# PT100_Module.net
KiCad netlist of a schematic drawn in EAGLE
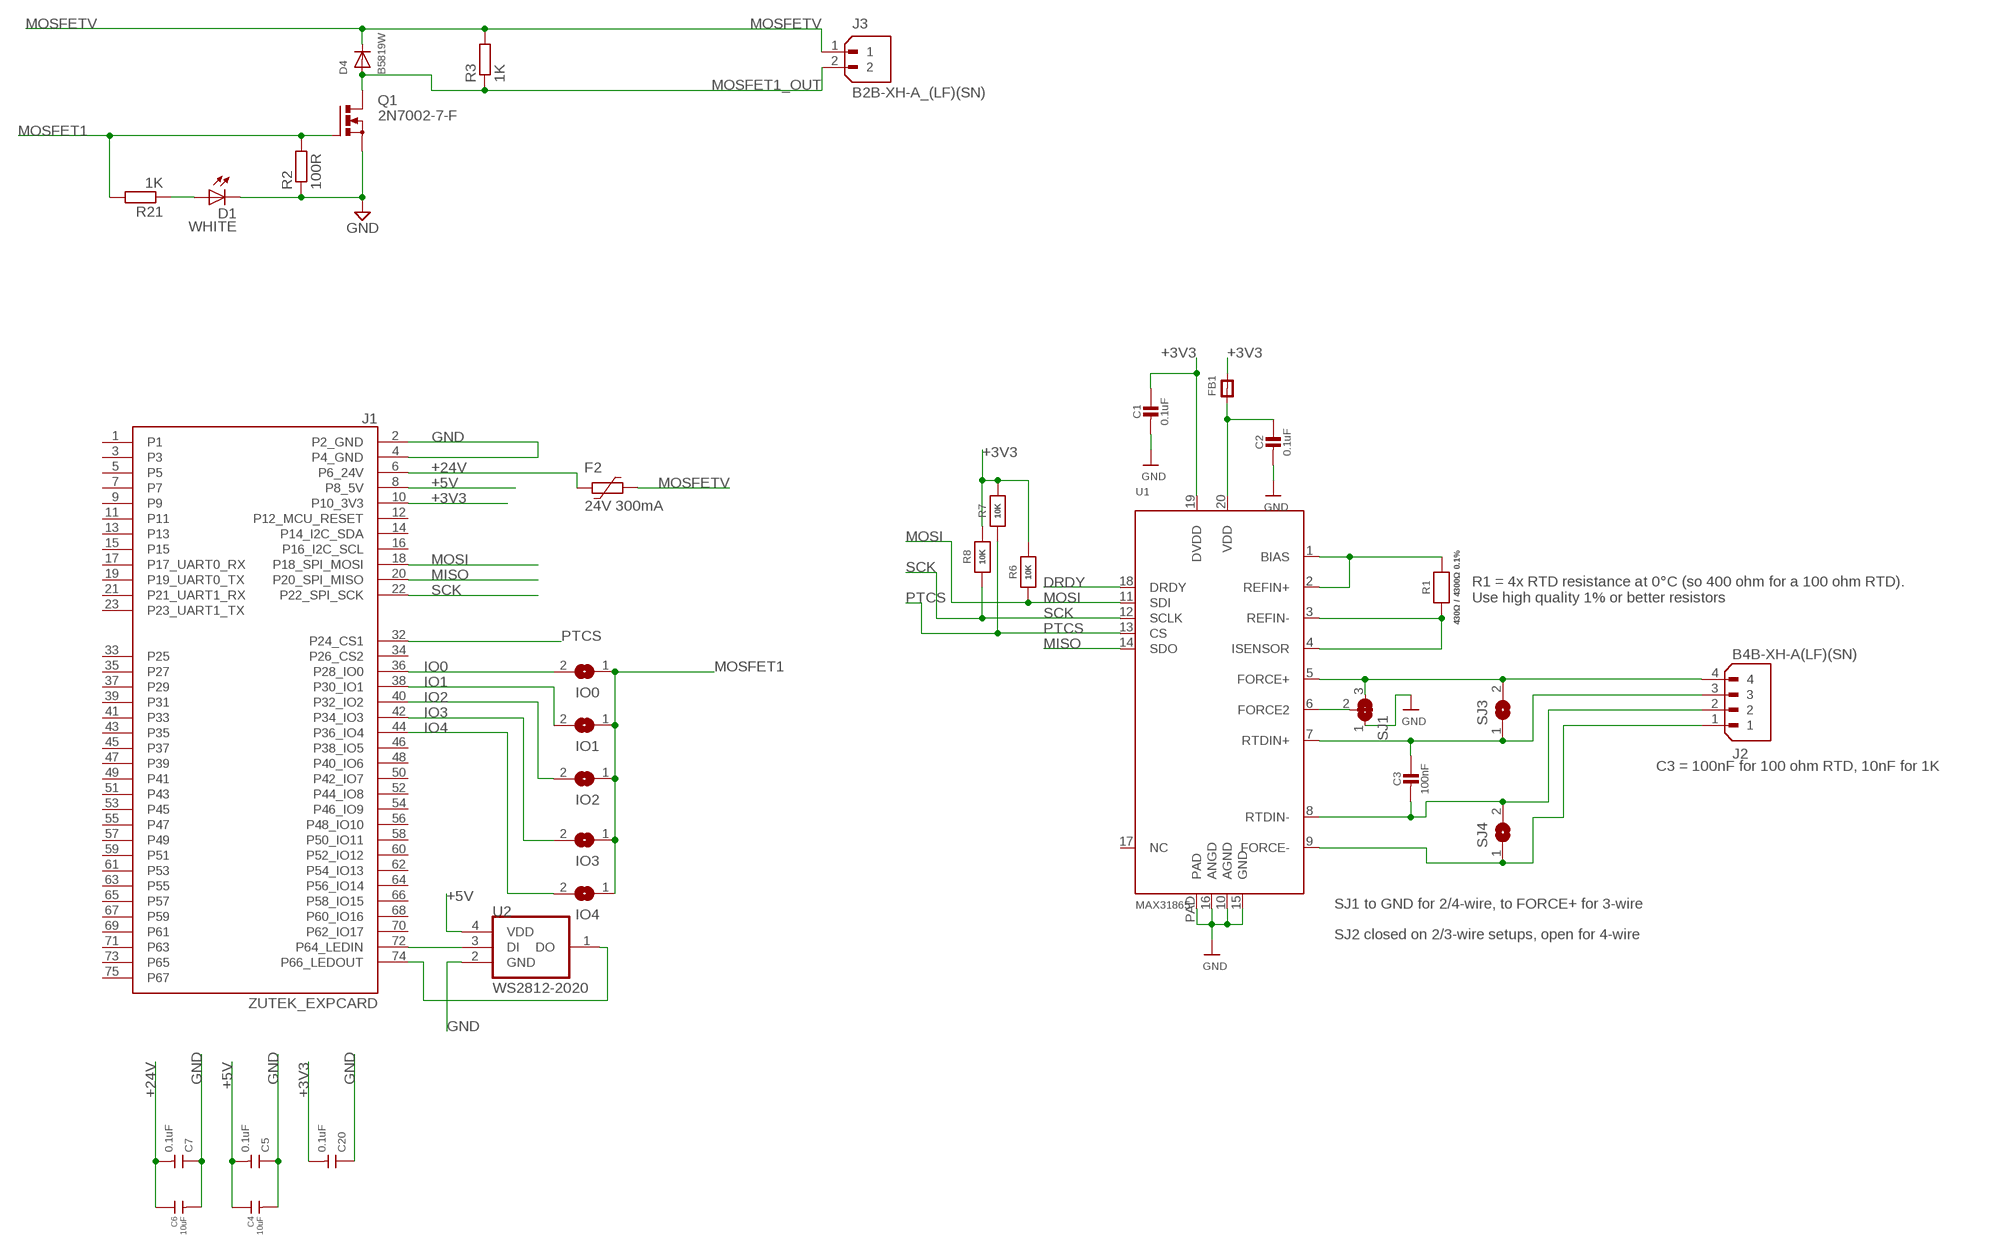
[diagram p0: schematic, sheet 1]

(export (version "E")
  (design (tool "Eeschema 10.0.6"))
  (components
    (comp (ref "C1")
      (value "0.1uF")
      (footprint "eagle-import:0805-NO")
      (libsource (lib "eagle-import") (part "CAP_CERAMIC0805-NOOUTLINE"))
    )
    (comp (ref "C2")
      (value "0.1uF")
      (footprint "eagle-import:0805-NO")
      (libsource (lib "eagle-import") (part "CAP_CERAMIC0805-NOOUTLINE"))
    )
    (comp (ref "C3")
      (value "100nF")
      (footprint "eagle-import:0805-NO")
      (libsource (lib "eagle-import") (part "CAP_CERAMIC0805-NOOUTLINE"))
    )
    (comp (ref "C4")
      (value "10uF")
      (footprint "eagle-import:C1206")
      (libsource (lib "eagle-import") (part "C-1206"))
    )
    (comp (ref "C5")
      (value "0.1uF")
      (footprint "eagle-import:DISCRETE_C0603")
      (libsource (lib "eagle-import") (part "DISCRETE_C-0603"))
    )
    (comp (ref "C6")
      (value "10uF")
      (footprint "eagle-import:C1206")
      (libsource (lib "eagle-import") (part "C-1206"))
    )
    (comp (ref "C7")
      (value "0.1uF")
      (footprint "eagle-import:DISCRETE_C0603")
      (libsource (lib "eagle-import") (part "DISCRETE_C-0603"))
    )
    (comp (ref "C20")
      (value "0.1uF")
      (footprint "eagle-import:DISCRETE_C0603")
      (libsource (lib "eagle-import") (part "DISCRETE_C-0603"))
    )
    (comp (ref "D1")
      (value "WHITE")
      (footprint "eagle-import:CHIP-LED0603")
      (libsource (lib "eagle-import") (part "LEDCHIP-LED0603"))
    )
    (comp (ref "D4")
      (value "B5819W")
      (footprint "eagle-import:SOD123FL")
      (fields (field (name "MF") "Microdiode Electronics"))
      (libsource (lib "eagle-import") (part "B5819W"))
    )
    (comp (ref "F2")
      (value "24V 300mA")
      (footprint "eagle-import:1206L")
      (fields (field (name "MF") "Littelfuse") (field (name "MPN") "1206L050"))
      (libsource (lib "eagle-import") (part "?1206L050"))
    )
    (comp (ref "FB1")
      (value "FERRITE-0805NO")
      (footprint "eagle-import:0805-NO")
      (libsource (lib "eagle-import") (part "FERRITE-0805NO"))
    )
    (comp (ref "IO0")
      (value "SOLDERJUMPERCLOSED")
      (footprint "eagle-import:SOLDERJUMPER_CLOSEDWIRE")
      (libsource (lib "eagle-import") (part "SOLDERJUMPERCLOSED"))
    )
    (comp (ref "IO1")
      (value "SOLDERJUMPER")
      (footprint "eagle-import:SOLDERJUMPER_ARROW_NOPASTE")
      (libsource (lib "eagle-import") (part "SOLDERJUMPER"))
    )
    (comp (ref "IO2")
      (value "SOLDERJUMPER")
      (footprint "eagle-import:SOLDERJUMPER_ARROW_NOPASTE")
      (libsource (lib "eagle-import") (part "SOLDERJUMPER"))
    )
    (comp (ref "IO3")
      (value "SOLDERJUMPER")
      (footprint "eagle-import:SOLDERJUMPER_ARROW_NOPASTE")
      (libsource (lib "eagle-import") (part "SOLDERJUMPER"))
    )
    (comp (ref "IO4")
      (value "SOLDERJUMPER")
      (footprint "eagle-import:SOLDERJUMPER_ARROW_NOPASTE")
      (libsource (lib "eagle-import") (part "SOLDERJUMPER"))
    )
    (comp (ref "J1")
      (value "ZUTEK_EXPCARD")
      (footprint "eagle-import:M.2-CARD-E-22-ZUTEK")
      (libsource (lib "eagle-import") (part "ZUTEK_EXPCARD"))
    )
    (comp (ref "J2")
      (value "B4B-XH-A(LF)(SN)")
      (footprint "eagle-import:JST_B4B-XH-A(LF)(SN)")
      (fields (field (name "MF") "JST Sales") (field (name "MP") "B4B-XH-A (LF)(SN)"))
      (libsource (lib "eagle-import") (part "B4B-XH-A(LF)(SN)"))
    )
    (comp (ref "J3")
      (value "B2B-XH-A_(LF)(SN)")
      (footprint "eagle-import:JST_B2B-XH-A_(LF)(SN)")
      (fields (field (name "MF") "JST Sales") (field (name "MP") "B2B-XH-A (LF)(SN)"))
      (libsource (lib "eagle-import") (part "B2B-XH-A_(LF)(SN)"))
    )
    (comp (ref "Q1")
      (value "2N7002-7-F")
      (footprint "eagle-import:SOT-23")
      (libsource (lib "eagle-import") (part "2N7002-7-F"))
    )
    (comp (ref "R1")
      (value "430Ω / 4300Ω 0.1%")
      (footprint "eagle-import:0805-NO")
      (libsource (lib "eagle-import") (part "RESISTOR0805_NOOUTLINE"))
    )
    (comp (ref "R2")
      (value "100R")
      (footprint "eagle-import:R0402")
      (libsource (lib "eagle-import") (part "R-EU_R0402"))
    )
    (comp (ref "R3")
      (value "1K")
      (footprint "eagle-import:R0402")
      (fields (field (name "LCSC_PART") "C11702 "))
      (libsource (lib "eagle-import") (part "R-EU_R0402"))
    )
    (comp (ref "R6")
      (value "10K")
      (footprint "eagle-import:_0402")
      (libsource (lib "eagle-import") (part "RESISTOR_0402"))
    )
    (comp (ref "R7")
      (value "10K")
      (footprint "eagle-import:_0402")
      (libsource (lib "eagle-import") (part "RESISTOR_0402"))
    )
    (comp (ref "R8")
      (value "10K")
      (footprint "eagle-import:_0402")
      (libsource (lib "eagle-import") (part "RESISTOR_0402"))
    )
    (comp (ref "R21")
      (value "1K")
      (footprint "eagle-import:R0402")
      (libsource (lib "eagle-import") (part "R-EU_R0402"))
    )
    (comp (ref "SJ1")
      (value "SOLDERJUMPER_2WAY")
      (footprint "eagle-import:SOLDERJUMPER_2WAY_OPEN_NOPASTE")
      (libsource (lib "eagle-import") (part "SOLDERJUMPER_2WAY"))
    )
    (comp (ref "SJ3")
      (value "SOLDERJUMPER")
      (footprint "eagle-import:SOLDERJUMPER_ARROW_NOPASTE")
      (libsource (lib "eagle-import") (part "SOLDERJUMPER"))
    )
    (comp (ref "SJ4")
      (value "SOLDERJUMPER")
      (footprint "eagle-import:SOLDERJUMPER_ARROW_NOPASTE")
      (libsource (lib "eagle-import") (part "SOLDERJUMPER"))
    )
    (comp (ref "U1")
      (value "MAX31865")
      (footprint "eagle-import:QFN20_4MM_0.65MM")
      (libsource (lib "eagle-import") (part "TEMP_MAX31865"))
    )
    (comp (ref "U2")
      (value "WS2812-2020")
      (footprint "eagle-import:LED_WS2812-2020")
      (fields (field (name "MF") "Worldsemi"))
      (libsource (lib "eagle-import") (part "WS2812-2020"))
    )
  )
  (nets
    (net (code "1") (name "/+3V3") (class "Default")
      (node (ref "C1") (pin "1") (pinfunction "1_1") (pintype "passive"))
      (node (ref "C20") (pin "2") (pinfunction "2_2") (pintype "passive"))
      (node (ref "FB1") (pin "2") (pinfunction "P$2_2") (pintype "passive"))
      (node (ref "J1") (pin "10") (pinfunction "P10_3V3_10") (pintype "bidirectional"))
      (node (ref "R6") (pin "2") (pinfunction "2_2") (pintype "passive"))
      (node (ref "R7") (pin "2") (pinfunction "2_2") (pintype "passive"))
      (node (ref "R8") (pin "2") (pinfunction "2_2") (pintype "passive"))
      (node (ref "U1") (pin "19") (pinfunction "DVDD_19") (pintype "power_in"))
    )
    (net (code "2") (name "/+5V") (class "Default")
      (node (ref "C4") (pin "1") (pinfunction "1_1") (pintype "passive"))
      (node (ref "C5") (pin "2") (pinfunction "2_2") (pintype "passive"))
      (node (ref "J1") (pin "8") (pinfunction "P8_5V_8") (pintype "bidirectional"))
      (node (ref "U2") (pin "4") (pinfunction "VDD_4") (pintype "power_in"))
    )
    (net (code "3") (name "/+24V") (class "Default")
      (node (ref "C6") (pin "1") (pinfunction "1_1") (pintype "passive"))
      (node (ref "C7") (pin "2") (pinfunction "2_2") (pintype "passive"))
      (node (ref "F2") (pin "2") (pinfunction "2_2") (pintype "passive"))
      (node (ref "J1") (pin "6") (pinfunction "P6_24V_6") (pintype "bidirectional"))
    )
    (net (code "4") (name "/DRDY") (class "Default")
      (node (ref "U1") (pin "18") (pinfunction "DRDY_18") (pintype "output"))
    )
    (net (code "5") (name "/IO0") (class "Default")
      (node (ref "IO0") (pin "2") (pinfunction "2_2") (pintype "passive"))
      (node (ref "J1") (pin "36") (pinfunction "P28_IO0_36") (pintype "bidirectional"))
    )
    (net (code "6") (name "/IO1") (class "Default")
      (node (ref "IO1") (pin "2") (pinfunction "2_2") (pintype "passive"))
      (node (ref "J1") (pin "38") (pinfunction "P30_IO1_38") (pintype "bidirectional"))
    )
    (net (code "7") (name "/IO2") (class "Default")
      (node (ref "IO2") (pin "2") (pinfunction "2_2") (pintype "passive"))
      (node (ref "J1") (pin "40") (pinfunction "P32_IO2_40") (pintype "bidirectional"))
    )
    (net (code "8") (name "/IO3") (class "Default")
      (node (ref "IO3") (pin "2") (pinfunction "2_2") (pintype "passive"))
      (node (ref "J1") (pin "42") (pinfunction "P34_IO3_42") (pintype "bidirectional"))
    )
    (net (code "9") (name "/IO4") (class "Default")
      (node (ref "IO4") (pin "2") (pinfunction "2_2") (pintype "passive"))
      (node (ref "J1") (pin "44") (pinfunction "P36_IO4_44") (pintype "bidirectional"))
    )
    (net (code "10") (name "/MISO") (class "Default")
      (node (ref "J1") (pin "20") (pinfunction "P20_SPI_MISO_20") (pintype "bidirectional"))
      (node (ref "U1") (pin "14") (pinfunction "SDO_14") (pintype "output"))
    )
    (net (code "11") (name "/MOSFET1") (class "Default")
      (node (ref "IO0") (pin "1") (pinfunction "1_1") (pintype "passive"))
      (node (ref "IO1") (pin "1") (pinfunction "1_1") (pintype "passive"))
      (node (ref "IO2") (pin "1") (pinfunction "1_1") (pintype "passive"))
      (node (ref "IO3") (pin "1") (pinfunction "1_1") (pintype "passive"))
      (node (ref "IO4") (pin "1") (pinfunction "1_1") (pintype "passive"))
      (node (ref "Q1") (pin "P1") (pinfunction "G_P1") (pintype "passive"))
      (node (ref "R2") (pin "2") (pinfunction "2_2") (pintype "passive"))
      (node (ref "R21") (pin "2") (pinfunction "2_2") (pintype "passive"))
    )
    (net (code "12") (name "/MOSFET1_OUT") (class "Default")
      (node (ref "D4") (pin "A") (pinfunction "A_A") (pintype "passive"))
      (node (ref "J3") (pin "2") (pinfunction "2_2") (pintype "passive"))
      (node (ref "Q1") (pin "P3") (pinfunction "D_P3") (pintype "passive"))
      (node (ref "R3") (pin "1") (pinfunction "1_1") (pintype "passive"))
    )
    (net (code "13") (name "/MOSFETV") (class "Default")
      (node (ref "D4") (pin "C") (pinfunction "C_C") (pintype "passive"))
      (node (ref "F2") (pin "1") (pinfunction "1_1") (pintype "passive"))
      (node (ref "J3") (pin "1") (pinfunction "1_1") (pintype "passive"))
      (node (ref "R3") (pin "2") (pinfunction "2_2") (pintype "passive"))
    )
    (net (code "14") (name "/MOSI") (class "Default")
      (node (ref "J1") (pin "18") (pinfunction "P18_SPI_MOSI_18") (pintype "bidirectional"))
      (node (ref "R6") (pin "1") (pinfunction "1_1") (pintype "passive"))
      (node (ref "U1") (pin "11") (pinfunction "SDI_11") (pintype "input"))
    )
    (net (code "15") (name "/PTCS") (class "Default")
      (node (ref "J1") (pin "32") (pinfunction "P24_CS1_32") (pintype "bidirectional"))
      (node (ref "R7") (pin "1") (pinfunction "1_1") (pintype "passive"))
      (node (ref "U1") (pin "13") (pinfunction "CS_13") (pintype "input"))
    )
    (net (code "16") (name "/SCK") (class "Default")
      (node (ref "J1") (pin "22") (pinfunction "P22_SPI_SCK_22") (pintype "bidirectional"))
      (node (ref "R8") (pin "1") (pinfunction "1_1") (pintype "passive"))
      (node (ref "U1") (pin "12") (pinfunction "SCLK_12") (pintype "input"))
    )
    (net (code "17") (name "GND") (class "Default")
      (node (ref "C1") (pin "2") (pinfunction "2_2") (pintype "passive"))
      (node (ref "C2") (pin "2") (pinfunction "2_2") (pintype "passive"))
      (node (ref "C20") (pin "1") (pinfunction "1_1") (pintype "passive"))
      (node (ref "C4") (pin "2") (pinfunction "2_2") (pintype "passive"))
      (node (ref "C5") (pin "1") (pinfunction "1_1") (pintype "passive"))
      (node (ref "C6") (pin "2") (pinfunction "2_2") (pintype "passive"))
      (node (ref "C7") (pin "1") (pinfunction "1_1") (pintype "passive"))
      (node (ref "D1") (pin "C") (pinfunction "C_C") (pintype "passive"))
      (node (ref "J1") (pin "2") (pinfunction "P2_GND_2") (pintype "bidirectional"))
      (node (ref "J1") (pin "4") (pinfunction "P4_GND_4") (pintype "bidirectional"))
      (node (ref "Q1") (pin "P2") (pinfunction "S_P2") (pintype "passive"))
      (node (ref "R2") (pin "1") (pinfunction "1_1") (pintype "passive"))
      (node (ref "SJ1") (pin "1") (pinfunction "1_1") (pintype "passive"))
      (node (ref "U1") (pin "10") (pinfunction "AGND_10") (pintype "power_in"))
      (node (ref "U1") (pin "15") (pinfunction "GND_15") (pintype "power_in"))
      (node (ref "U1") (pin "16") (pinfunction "ANGD_16") (pintype "power_in"))
      (node (ref "U1") (pin "PAD") (pinfunction "PAD_PAD") (pintype "power_in"))
      (node (ref "U2") (pin "2") (pinfunction "GND_2") (pintype "power_in"))
    )
    (net (code "18") (name "Net-(D1-PadA)") (class "Default")
      (node (ref "D1") (pin "A") (pinfunction "A_A") (pintype "passive"))
      (node (ref "R21") (pin "1") (pinfunction "1_1") (pintype "passive"))
    )
    (net (code "19") (name "Net-(FB1-P$1)") (class "Default")
      (node (ref "C2") (pin "1") (pinfunction "1_1") (pintype "passive"))
      (node (ref "FB1") (pin "1") (pinfunction "P$1_1") (pintype "passive"))
      (node (ref "U1") (pin "20") (pinfunction "VDD_20") (pintype "power_in"))
    )
    (net (code "20") (name "Net-(J1-P64_LEDIN)") (class "Default")
      (node (ref "J1") (pin "72") (pinfunction "P64_LEDIN_72") (pintype "bidirectional"))
      (node (ref "U2") (pin "3") (pinfunction "DI_3") (pintype "input"))
    )
    (net (code "21") (name "Net-(J1-P66_LEDOUT)") (class "Default")
      (node (ref "J1") (pin "74") (pinfunction "P66_LEDOUT_74") (pintype "bidirectional"))
      (node (ref "U2") (pin "1") (pinfunction "DO_1") (pintype "output"))
    )
    (net (code "22") (name "Net-(U1-BIAS)") (class "Default")
      (node (ref "R1") (pin "2") (pinfunction "2_2") (pintype "passive"))
      (node (ref "U1") (pin "1") (pinfunction "BIAS_1") (pintype "output"))
      (node (ref "U1") (pin "2") (pinfunction "REFIN+_2") (pintype "bidirectional"))
    )
    (net (code "23") (name "Net-(U1-FORCE+)") (class "Default")
      (node (ref "J2") (pin "4") (pinfunction "4_4") (pintype "passive"))
      (node (ref "SJ1") (pin "3") (pinfunction "3_3") (pintype "passive"))
      (node (ref "SJ3") (pin "2") (pinfunction "2_2") (pintype "passive"))
      (node (ref "U1") (pin "5") (pinfunction "FORCE+_5") (pintype "output"))
    )
    (net (code "24") (name "Net-(U1-FORCE-)") (class "Default")
      (node (ref "J2") (pin "1") (pinfunction "1_1") (pintype "passive"))
      (node (ref "SJ4") (pin "1") (pinfunction "1_1") (pintype "passive"))
      (node (ref "U1") (pin "9") (pinfunction "FORCE-_9") (pintype "input"))
    )
    (net (code "25") (name "Net-(U1-FORCE2)") (class "Default")
      (node (ref "SJ1") (pin "2") (pinfunction "2_2") (pintype "passive"))
      (node (ref "U1") (pin "6") (pinfunction "FORCE2_6") (pintype "bidirectional"))
    )
    (net (code "26") (name "Net-(U1-ISENSOR)") (class "Default")
      (node (ref "R1") (pin "1") (pinfunction "1_1") (pintype "passive"))
      (node (ref "U1") (pin "3") (pinfunction "REFIN-_3") (pintype "bidirectional"))
      (node (ref "U1") (pin "4") (pinfunction "ISENSOR_4") (pintype "input"))
    )
    (net (code "27") (name "Net-(U1-RTDIN+)") (class "Default")
      (node (ref "C3") (pin "1") (pinfunction "1_1") (pintype "passive"))
      (node (ref "J2") (pin "3") (pinfunction "3_3") (pintype "passive"))
      (node (ref "SJ3") (pin "1") (pinfunction "1_1") (pintype "passive"))
      (node (ref "U1") (pin "7") (pinfunction "RTDIN+_7") (pintype "bidirectional"))
    )
    (net (code "28") (name "Net-(U1-RTDIN-)") (class "Default")
      (node (ref "C3") (pin "2") (pinfunction "2_2") (pintype "passive"))
      (node (ref "J2") (pin "2") (pinfunction "2_2") (pintype "passive"))
      (node (ref "SJ4") (pin "2") (pinfunction "2_2") (pintype "passive"))
      (node (ref "U1") (pin "8") (pinfunction "RTDIN-_8") (pintype "bidirectional"))
    )
    (net (code "29") (name "unconnected-(J1-P1-Pad1)") (class "Default")
      (node (ref "J1") (pin "1") (pinfunction "P1_1") (pintype "bidirectional"))
    )
    (net (code "30") (name "unconnected-(J1-P3-Pad3)") (class "Default")
      (node (ref "J1") (pin "3") (pinfunction "P3_3") (pintype "bidirectional"))
    )
    (net (code "31") (name "unconnected-(J1-P5-Pad5)") (class "Default")
      (node (ref "J1") (pin "5") (pinfunction "P5_5") (pintype "bidirectional"))
    )
    (net (code "32") (name "unconnected-(J1-P7-Pad7)") (class "Default")
      (node (ref "J1") (pin "7") (pinfunction "P7_7") (pintype "bidirectional"))
    )
    (net (code "33") (name "unconnected-(J1-P9-Pad9)") (class "Default")
      (node (ref "J1") (pin "9") (pinfunction "P9_9") (pintype "bidirectional"))
    )
    (net (code "34") (name "unconnected-(J1-P11-Pad11)") (class "Default")
      (node (ref "J1") (pin "11") (pinfunction "P11_11") (pintype "bidirectional"))
    )
    (net (code "35") (name "unconnected-(J1-P12_MCU_RESET-Pad12)") (class "Default")
      (node (ref "J1") (pin "12") (pinfunction "P12_MCU_RESET_12") (pintype "bidirectional"))
    )
    (net (code "36") (name "unconnected-(J1-P13-Pad13)") (class "Default")
      (node (ref "J1") (pin "13") (pinfunction "P13_13") (pintype "bidirectional"))
    )
    (net (code "37") (name "unconnected-(J1-P14_I2C_SDA-Pad14)") (class "Default")
      (node (ref "J1") (pin "14") (pinfunction "P14_I2C_SDA_14") (pintype "bidirectional"))
    )
    (net (code "38") (name "unconnected-(J1-P15-Pad15)") (class "Default")
      (node (ref "J1") (pin "15") (pinfunction "P15_15") (pintype "bidirectional"))
    )
    (net (code "39") (name "unconnected-(J1-P16_I2C_SCL-Pad16)") (class "Default")
      (node (ref "J1") (pin "16") (pinfunction "P16_I2C_SCL_16") (pintype "bidirectional"))
    )
    (net (code "40") (name "unconnected-(J1-P17_UART0_RX-Pad17)") (class "Default")
      (node (ref "J1") (pin "17") (pinfunction "P17_UART0_RX_17") (pintype "bidirectional"))
    )
    (net (code "41") (name "unconnected-(J1-P19_UART0_TX-Pad19)") (class "Default")
      (node (ref "J1") (pin "19") (pinfunction "P19_UART0_TX_19") (pintype "bidirectional"))
    )
    (net (code "42") (name "unconnected-(J1-P21_UART1_RX-Pad21)") (class "Default")
      (node (ref "J1") (pin "21") (pinfunction "P21_UART1_RX_21") (pintype "bidirectional"))
    )
    (net (code "43") (name "unconnected-(J1-P23_UART1_TX-Pad23)") (class "Default")
      (node (ref "J1") (pin "23") (pinfunction "P23_UART1_TX_23") (pintype "bidirectional"))
    )
    (net (code "44") (name "unconnected-(J1-P25-Pad33)") (class "Default")
      (node (ref "J1") (pin "33") (pinfunction "P25_33") (pintype "bidirectional"))
    )
    (net (code "45") (name "unconnected-(J1-P26_CS2-Pad34)") (class "Default")
      (node (ref "J1") (pin "34") (pinfunction "P26_CS2_34") (pintype "bidirectional"))
    )
    (net (code "46") (name "unconnected-(J1-P27-Pad35)") (class "Default")
      (node (ref "J1") (pin "35") (pinfunction "P27_35") (pintype "bidirectional"))
    )
    (net (code "47") (name "unconnected-(J1-P29-Pad37)") (class "Default")
      (node (ref "J1") (pin "37") (pinfunction "P29_37") (pintype "bidirectional"))
    )
    (net (code "48") (name "unconnected-(J1-P31-Pad39)") (class "Default")
      (node (ref "J1") (pin "39") (pinfunction "P31_39") (pintype "bidirectional"))
    )
    (net (code "49") (name "unconnected-(J1-P33-Pad41)") (class "Default")
      (node (ref "J1") (pin "41") (pinfunction "P33_41") (pintype "bidirectional"))
    )
    (net (code "50") (name "unconnected-(J1-P35-Pad43)") (class "Default")
      (node (ref "J1") (pin "43") (pinfunction "P35_43") (pintype "bidirectional"))
    )
    (net (code "51") (name "unconnected-(J1-P37-Pad45)") (class "Default")
      (node (ref "J1") (pin "45") (pinfunction "P37_45") (pintype "bidirectional"))
    )
    (net (code "52") (name "unconnected-(J1-P38_IO5-Pad46)") (class "Default")
      (node (ref "J1") (pin "46") (pinfunction "P38_IO5_46") (pintype "bidirectional"))
    )
    (net (code "53") (name "unconnected-(J1-P39-Pad47)") (class "Default")
      (node (ref "J1") (pin "47") (pinfunction "P39_47") (pintype "bidirectional"))
    )
    (net (code "54") (name "unconnected-(J1-P40_IO6-Pad48)") (class "Default")
      (node (ref "J1") (pin "48") (pinfunction "P40_IO6_48") (pintype "bidirectional"))
    )
    (net (code "55") (name "unconnected-(J1-P41-Pad49)") (class "Default")
      (node (ref "J1") (pin "49") (pinfunction "P41_49") (pintype "bidirectional"))
    )
    (net (code "56") (name "unconnected-(J1-P42_IO7-Pad50)") (class "Default")
      (node (ref "J1") (pin "50") (pinfunction "P42_IO7_50") (pintype "bidirectional"))
    )
    (net (code "57") (name "unconnected-(J1-P43-Pad51)") (class "Default")
      (node (ref "J1") (pin "51") (pinfunction "P43_51") (pintype "bidirectional"))
    )
    (net (code "58") (name "unconnected-(J1-P44_IO8-Pad52)") (class "Default")
      (node (ref "J1") (pin "52") (pinfunction "P44_IO8_52") (pintype "bidirectional"))
    )
    (net (code "59") (name "unconnected-(J1-P45-Pad53)") (class "Default")
      (node (ref "J1") (pin "53") (pinfunction "P45_53") (pintype "bidirectional"))
    )
    (net (code "60") (name "unconnected-(J1-P46_IO9-Pad54)") (class "Default")
      (node (ref "J1") (pin "54") (pinfunction "P46_IO9_54") (pintype "bidirectional"))
    )
    (net (code "61") (name "unconnected-(J1-P47-Pad55)") (class "Default")
      (node (ref "J1") (pin "55") (pinfunction "P47_55") (pintype "bidirectional"))
    )
    (net (code "62") (name "unconnected-(J1-P48_IO10-Pad56)") (class "Default")
      (node (ref "J1") (pin "56") (pinfunction "P48_IO10_56") (pintype "bidirectional"))
    )
    (net (code "63") (name "unconnected-(J1-P49-Pad57)") (class "Default")
      (node (ref "J1") (pin "57") (pinfunction "P49_57") (pintype "bidirectional"))
    )
    (net (code "64") (name "unconnected-(J1-P50_IO11-Pad58)") (class "Default")
      (node (ref "J1") (pin "58") (pinfunction "P50_IO11_58") (pintype "bidirectional"))
    )
    (net (code "65") (name "unconnected-(J1-P51-Pad59)") (class "Default")
      (node (ref "J1") (pin "59") (pinfunction "P51_59") (pintype "bidirectional"))
    )
    (net (code "66") (name "unconnected-(J1-P52_IO12-Pad60)") (class "Default")
      (node (ref "J1") (pin "60") (pinfunction "P52_IO12_60") (pintype "bidirectional"))
    )
    (net (code "67") (name "unconnected-(J1-P53-Pad61)") (class "Default")
      (node (ref "J1") (pin "61") (pinfunction "P53_61") (pintype "bidirectional"))
    )
    (net (code "68") (name "unconnected-(J1-P54_IO13-Pad62)") (class "Default")
      (node (ref "J1") (pin "62") (pinfunction "P54_IO13_62") (pintype "bidirectional"))
    )
    (net (code "69") (name "unconnected-(J1-P55-Pad63)") (class "Default")
      (node (ref "J1") (pin "63") (pinfunction "P55_63") (pintype "bidirectional"))
    )
    (net (code "70") (name "unconnected-(J1-P56_IO14-Pad64)") (class "Default")
      (node (ref "J1") (pin "64") (pinfunction "P56_IO14_64") (pintype "bidirectional"))
    )
    (net (code "71") (name "unconnected-(J1-P57-Pad65)") (class "Default")
      (node (ref "J1") (pin "65") (pinfunction "P57_65") (pintype "bidirectional"))
    )
    (net (code "72") (name "unconnected-(J1-P58_IO15-Pad66)") (class "Default")
      (node (ref "J1") (pin "66") (pinfunction "P58_IO15_66") (pintype "bidirectional"))
    )
    (net (code "73") (name "unconnected-(J1-P59-Pad67)") (class "Default")
      (node (ref "J1") (pin "67") (pinfunction "P59_67") (pintype "bidirectional"))
    )
    (net (code "74") (name "unconnected-(J1-P60_IO16-Pad68)") (class "Default")
      (node (ref "J1") (pin "68") (pinfunction "P60_IO16_68") (pintype "bidirectional"))
    )
    (net (code "75") (name "unconnected-(J1-P61-Pad69)") (class "Default")
      (node (ref "J1") (pin "69") (pinfunction "P61_69") (pintype "bidirectional"))
    )
    (net (code "76") (name "unconnected-(J1-P62_IO17-Pad70)") (class "Default")
      (node (ref "J1") (pin "70") (pinfunction "P62_IO17_70") (pintype "bidirectional"))
    )
    (net (code "77") (name "unconnected-(J1-P63-Pad71)") (class "Default")
      (node (ref "J1") (pin "71") (pinfunction "P63_71") (pintype "bidirectional"))
    )
    (net (code "78") (name "unconnected-(J1-P65-Pad73)") (class "Default")
      (node (ref "J1") (pin "73") (pinfunction "P65_73") (pintype "bidirectional"))
    )
    (net (code "79") (name "unconnected-(J1-P67-Pad75)") (class "Default")
      (node (ref "J1") (pin "75") (pinfunction "P67_75") (pintype "bidirectional"))
    )
    (net (code "80") (name "unconnected-(U1-NC-Pad17)") (class "Default")
      (node (ref "U1") (pin "17") (pinfunction "NC_17") (pintype "no_connect"))
    )
  )
)
